# BBB-Supply.net
KiCad netlist of a schematic drawn in Altium Designer
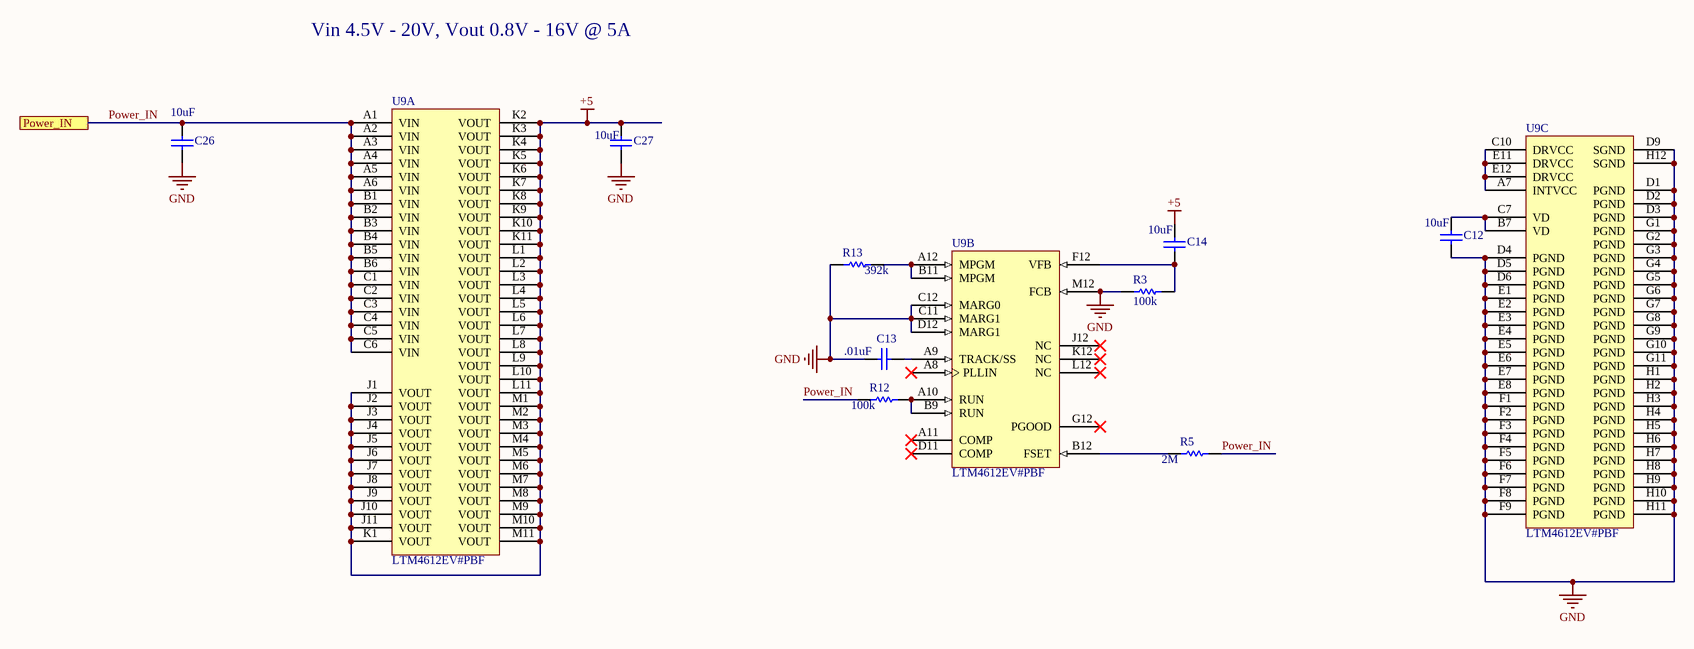
[diagram p0: BBB-Supply.SchDoc]

(export (version "E")
  (design (tool "Eeschema 10.0.6"))
  (components
    (comp (ref "C12")
      (value "10uF")
      (footprint "CAPC0805(2012)145_N")
      (description "CAP CER 10UF 25V X7R 0805")
      (fields
        (field (name "MANUFACTURER") "TDK")
        (field (name "MANUFACTURER PART NUMBER") "C2012X5R1V106K125AC")
      )
      (libsource (lib "Altium Content Vault") (part "CMP-1036-04795-1"))
    )
    (comp (ref "C13")
      (value ".01uF")
      (footprint "CAPC0805(2012)145_N")
      (fields
        (field (name "MANUFACTURER") "Yageo")
        (field (name "MANUFACTURER PART NUMBER") "AC0805KRX7R7BB103")
        (field (name "TOLERANCE") "±10%")
      )
      (libsource (lib "Altium Content Vault") (part "CMP-1036-04795-1"))
    )
    (comp (ref "C14")
      (value "10uF")
      (footprint "CAPC0805(2012)145_N")
      (description "CAP CER 10UF 25V X7R 0805")
      (fields
        (field (name "MANUFACTURER") "TDK")
        (field (name "MANUFACTURER PART NUMBER") "C2012X5R1V106K125AC")
      )
      (libsource (lib "Altium Content Vault") (part "CMP-1036-04795-1"))
    )
    (comp (ref "C26")
      (value "10uF")
      (footprint "CAPC0805(2012)145_N")
      (description "CAP CER 10UF 25V X7R 0805")
      (fields
        (field (name "MANUFACTURER") "TDK")
        (field (name "MANUFACTURER PART NUMBER") "C2012X5R1V106K125AC")
      )
      (libsource (lib "Altium Content Vault") (part "CMP-1036-04795-1"))
    )
    (comp (ref "C27")
      (value "10uF")
      (footprint "CAPC0805(2012)145_N")
      (description "CAP CER 10UF 25V X7R 0805")
      (fields
        (field (name "MANUFACTURER") "TDK")
        (field (name "MANUFACTURER PART NUMBER") "C2012X5R1V106K125AC")
      )
      (libsource (lib "Altium Content Vault") (part "CMP-1036-04795-1"))
    )
    (comp (ref "R3")
      (value "100k")
      (footprint "RESC0805(2012)_M")
      (description "RES SMD 0.8 OHM 1% 1/8W 0805")
      (libsource (lib "Altium Content Vault") (part "CMP-1013-00017-1"))
    )
    (comp (ref "R5")
      (value "2M")
      (footprint "RESC0805(2012)_M")
      (description "RES SMD 0.8 OHM 1% 1/8W 0805")
      (libsource (lib "Altium Content Vault") (part "CMP-1013-00017-1"))
    )
    (comp (ref "R12")
      (value "100k")
      (footprint "RESC0805(2012)_M")
      (description "RES SMD 0.8 OHM 1% 1/8W 0805")
      (libsource (lib "Altium Content Vault") (part "CMP-1013-00017-1"))
    )
    (comp (ref "R13")
      (value "392k")
      (footprint "RESC0805(2012)_M")
      (description "RES SMD 0.8 OHM 1% 1/8W 0805")
      (libsource (lib "Altium Content Vault") (part "CMP-1013-00017-1"))
    )
    (comp (ref "U9")
      (value "LTM4612EV#PBF")
      (footprint "LT-LGA-133-05-08-1766_V")
      (fields (field (name "MANUFACTURER") "Linear Technology"))
      (libsource (lib "Altium Content Vault") (part "LT-LTM4612-LGA-133"))
    )
  )
  (nets
    (net (code "1") (name "+5") (class "Default")
      (node (ref "C14") (pin "1") (pinfunction "1_1") (pintype "passive"))
      (node (ref "C27") (pin "1") (pinfunction "1_1") (pintype "passive"))
      (node (ref "U9") (pin "J1") (pinfunction "VOUT_J1") (pintype "power_in"))
      (node (ref "U9") (pin "J10") (pinfunction "VOUT_J10") (pintype "power_in"))
      (node (ref "U9") (pin "J11") (pinfunction "VOUT_J11") (pintype "power_in"))
      (node (ref "U9") (pin "J2") (pinfunction "VOUT_J2") (pintype "power_in"))
      (node (ref "U9") (pin "J3") (pinfunction "VOUT_J3") (pintype "power_in"))
      (node (ref "U9") (pin "J4") (pinfunction "VOUT_J4") (pintype "power_in"))
      (node (ref "U9") (pin "J5") (pinfunction "VOUT_J5") (pintype "power_in"))
      (node (ref "U9") (pin "J6") (pinfunction "VOUT_J6") (pintype "power_in"))
      (node (ref "U9") (pin "J7") (pinfunction "VOUT_J7") (pintype "power_in"))
      (node (ref "U9") (pin "J8") (pinfunction "VOUT_J8") (pintype "power_in"))
      (node (ref "U9") (pin "J9") (pinfunction "VOUT_J9") (pintype "power_in"))
      (node (ref "U9") (pin "K1") (pinfunction "VOUT_K1") (pintype "power_in"))
      (node (ref "U9") (pin "K10") (pinfunction "VOUT_K10") (pintype "power_in"))
      (node (ref "U9") (pin "K11") (pinfunction "VOUT_K11") (pintype "power_in"))
      (node (ref "U9") (pin "K2") (pinfunction "VOUT_K2") (pintype "power_in"))
      (node (ref "U9") (pin "K3") (pinfunction "VOUT_K3") (pintype "power_in"))
      (node (ref "U9") (pin "K4") (pinfunction "VOUT_K4") (pintype "power_in"))
      (node (ref "U9") (pin "K5") (pinfunction "VOUT_K5") (pintype "power_in"))
      (node (ref "U9") (pin "K6") (pinfunction "VOUT_K6") (pintype "power_in"))
      (node (ref "U9") (pin "K7") (pinfunction "VOUT_K7") (pintype "power_in"))
      (node (ref "U9") (pin "K8") (pinfunction "VOUT_K8") (pintype "power_in"))
      (node (ref "U9") (pin "K9") (pinfunction "VOUT_K9") (pintype "power_in"))
      (node (ref "U9") (pin "L1") (pinfunction "VOUT_L1") (pintype "power_in"))
      (node (ref "U9") (pin "L10") (pinfunction "VOUT_L10") (pintype "power_in"))
      (node (ref "U9") (pin "L11") (pinfunction "VOUT_L11") (pintype "power_in"))
      (node (ref "U9") (pin "L2") (pinfunction "VOUT_L2") (pintype "power_in"))
      (node (ref "U9") (pin "L3") (pinfunction "VOUT_L3") (pintype "power_in"))
      (node (ref "U9") (pin "L4") (pinfunction "VOUT_L4") (pintype "power_in"))
      (node (ref "U9") (pin "L5") (pinfunction "VOUT_L5") (pintype "power_in"))
      (node (ref "U9") (pin "L6") (pinfunction "VOUT_L6") (pintype "power_in"))
      (node (ref "U9") (pin "L7") (pinfunction "VOUT_L7") (pintype "power_in"))
      (node (ref "U9") (pin "L8") (pinfunction "VOUT_L8") (pintype "power_in"))
      (node (ref "U9") (pin "L9") (pinfunction "VOUT_L9") (pintype "power_in"))
      (node (ref "U9") (pin "M1") (pinfunction "VOUT_M1") (pintype "power_in"))
      (node (ref "U9") (pin "M10") (pinfunction "VOUT_M10") (pintype "power_in"))
      (node (ref "U9") (pin "M11") (pinfunction "VOUT_M11") (pintype "power_in"))
      (node (ref "U9") (pin "M2") (pinfunction "VOUT_M2") (pintype "power_in"))
      (node (ref "U9") (pin "M3") (pinfunction "VOUT_M3") (pintype "power_in"))
      (node (ref "U9") (pin "M4") (pinfunction "VOUT_M4") (pintype "power_in"))
      (node (ref "U9") (pin "M5") (pinfunction "VOUT_M5") (pintype "power_in"))
      (node (ref "U9") (pin "M6") (pinfunction "VOUT_M6") (pintype "power_in"))
      (node (ref "U9") (pin "M7") (pinfunction "VOUT_M7") (pintype "power_in"))
      (node (ref "U9") (pin "M8") (pinfunction "VOUT_M8") (pintype "power_in"))
      (node (ref "U9") (pin "M9") (pinfunction "VOUT_M9") (pintype "power_in"))
    )
    (net (code "2") (name "/Power_IN") (class "Default")
      (node (ref "C26") (pin "1") (pinfunction "1_1") (pintype "passive"))
      (node (ref "R12") (pin "2") (pinfunction "2_2") (pintype "passive"))
      (node (ref "R5") (pin "1") (pinfunction "1_1") (pintype "passive"))
      (node (ref "U9") (pin "A1") (pinfunction "VIN_A1") (pintype "power_in"))
      (node (ref "U9") (pin "A2") (pinfunction "VIN_A2") (pintype "power_in"))
      (node (ref "U9") (pin "A3") (pinfunction "VIN_A3") (pintype "power_in"))
      (node (ref "U9") (pin "A4") (pinfunction "VIN_A4") (pintype "power_in"))
      (node (ref "U9") (pin "A5") (pinfunction "VIN_A5") (pintype "power_in"))
      (node (ref "U9") (pin "A6") (pinfunction "VIN_A6") (pintype "power_in"))
      (node (ref "U9") (pin "B1") (pinfunction "VIN_B1") (pintype "power_in"))
      (node (ref "U9") (pin "B2") (pinfunction "VIN_B2") (pintype "power_in"))
      (node (ref "U9") (pin "B3") (pinfunction "VIN_B3") (pintype "power_in"))
      (node (ref "U9") (pin "B4") (pinfunction "VIN_B4") (pintype "power_in"))
      (node (ref "U9") (pin "B5") (pinfunction "VIN_B5") (pintype "power_in"))
      (node (ref "U9") (pin "B6") (pinfunction "VIN_B6") (pintype "power_in"))
      (node (ref "U9") (pin "C1") (pinfunction "VIN_C1") (pintype "power_in"))
      (node (ref "U9") (pin "C2") (pinfunction "VIN_C2") (pintype "power_in"))
      (node (ref "U9") (pin "C3") (pinfunction "VIN_C3") (pintype "power_in"))
      (node (ref "U9") (pin "C4") (pinfunction "VIN_C4") (pintype "power_in"))
      (node (ref "U9") (pin "C5") (pinfunction "VIN_C5") (pintype "power_in"))
      (node (ref "U9") (pin "C6") (pinfunction "VIN_C6") (pintype "power_in"))
    )
    (net (code "3") (name "GND") (class "Default")
      (node (ref "C12") (pin "2") (pinfunction "2_2") (pintype "passive"))
      (node (ref "C13") (pin "1") (pinfunction "1_1") (pintype "passive"))
      (node (ref "C26") (pin "2") (pinfunction "2_2") (pintype "passive"))
      (node (ref "C27") (pin "2") (pinfunction "2_2") (pintype "passive"))
      (node (ref "R13") (pin "2") (pinfunction "2_2") (pintype "passive"))
      (node (ref "R3") (pin "1") (pinfunction "1_1") (pintype "passive"))
      (node (ref "U9") (pin "C11") (pinfunction "MARG1_C11") (pintype "input"))
      (node (ref "U9") (pin "C12") (pinfunction "MARG0_C12") (pintype "input"))
      (node (ref "U9") (pin "D1") (pinfunction "PGND_D1") (pintype "power_in"))
      (node (ref "U9") (pin "D12") (pinfunction "MARG1_D12") (pintype "input"))
      (node (ref "U9") (pin "D2") (pinfunction "PGND_D2") (pintype "power_in"))
      (node (ref "U9") (pin "D3") (pinfunction "PGND_D3") (pintype "power_in"))
      (node (ref "U9") (pin "D4") (pinfunction "PGND_D4") (pintype "power_in"))
      (node (ref "U9") (pin "D5") (pinfunction "PGND_D5") (pintype "power_in"))
      (node (ref "U9") (pin "D6") (pinfunction "PGND_D6") (pintype "power_in"))
      (node (ref "U9") (pin "D9") (pinfunction "SGND_D9") (pintype "power_in"))
      (node (ref "U9") (pin "E1") (pinfunction "PGND_E1") (pintype "power_in"))
      (node (ref "U9") (pin "E2") (pinfunction "PGND_E2") (pintype "power_in"))
      (node (ref "U9") (pin "E3") (pinfunction "PGND_E3") (pintype "power_in"))
      (node (ref "U9") (pin "E4") (pinfunction "PGND_E4") (pintype "power_in"))
      (node (ref "U9") (pin "E5") (pinfunction "PGND_E5") (pintype "power_in"))
      (node (ref "U9") (pin "E6") (pinfunction "PGND_E6") (pintype "power_in"))
      (node (ref "U9") (pin "E7") (pinfunction "PGND_E7") (pintype "power_in"))
      (node (ref "U9") (pin "E8") (pinfunction "PGND_E8") (pintype "power_in"))
      (node (ref "U9") (pin "F1") (pinfunction "PGND_F1") (pintype "power_in"))
      (node (ref "U9") (pin "F2") (pinfunction "PGND_F2") (pintype "power_in"))
      (node (ref "U9") (pin "F3") (pinfunction "PGND_F3") (pintype "power_in"))
      (node (ref "U9") (pin "F4") (pinfunction "PGND_F4") (pintype "power_in"))
      (node (ref "U9") (pin "F5") (pinfunction "PGND_F5") (pintype "power_in"))
      (node (ref "U9") (pin "F6") (pinfunction "PGND_F6") (pintype "power_in"))
      (node (ref "U9") (pin "F7") (pinfunction "PGND_F7") (pintype "power_in"))
      (node (ref "U9") (pin "F8") (pinfunction "PGND_F8") (pintype "power_in"))
      (node (ref "U9") (pin "F9") (pinfunction "PGND_F9") (pintype "power_in"))
      (node (ref "U9") (pin "G1") (pinfunction "PGND_G1") (pintype "power_in"))
      (node (ref "U9") (pin "G10") (pinfunction "PGND_G10") (pintype "power_in"))
      (node (ref "U9") (pin "G11") (pinfunction "PGND_G11") (pintype "power_in"))
      (node (ref "U9") (pin "G2") (pinfunction "PGND_G2") (pintype "power_in"))
      (node (ref "U9") (pin "G3") (pinfunction "PGND_G3") (pintype "power_in"))
      (node (ref "U9") (pin "G4") (pinfunction "PGND_G4") (pintype "power_in"))
      (node (ref "U9") (pin "G5") (pinfunction "PGND_G5") (pintype "power_in"))
      (node (ref "U9") (pin "G6") (pinfunction "PGND_G6") (pintype "power_in"))
      (node (ref "U9") (pin "G7") (pinfunction "PGND_G7") (pintype "power_in"))
      (node (ref "U9") (pin "G8") (pinfunction "PGND_G8") (pintype "power_in"))
      (node (ref "U9") (pin "G9") (pinfunction "PGND_G9") (pintype "power_in"))
      (node (ref "U9") (pin "H1") (pinfunction "PGND_H1") (pintype "power_in"))
      (node (ref "U9") (pin "H10") (pinfunction "PGND_H10") (pintype "power_in"))
      (node (ref "U9") (pin "H11") (pinfunction "PGND_H11") (pintype "power_in"))
      (node (ref "U9") (pin "H12") (pinfunction "SGND_H12") (pintype "power_in"))
      (node (ref "U9") (pin "H2") (pinfunction "PGND_H2") (pintype "power_in"))
      (node (ref "U9") (pin "H3") (pinfunction "PGND_H3") (pintype "power_in"))
      (node (ref "U9") (pin "H4") (pinfunction "PGND_H4") (pintype "power_in"))
      (node (ref "U9") (pin "H5") (pinfunction "PGND_H5") (pintype "power_in"))
      (node (ref "U9") (pin "H6") (pinfunction "PGND_H6") (pintype "power_in"))
      (node (ref "U9") (pin "H7") (pinfunction "PGND_H7") (pintype "power_in"))
      (node (ref "U9") (pin "H8") (pinfunction "PGND_H8") (pintype "power_in"))
      (node (ref "U9") (pin "H9") (pinfunction "PGND_H9") (pintype "power_in"))
      (node (ref "U9") (pin "M12") (pinfunction "FCB_M12") (pintype "input"))
    )
    (net (code "4") (name "Net-(C12-Pad1)") (class "Default")
      (node (ref "C12") (pin "1") (pinfunction "1_1") (pintype "passive"))
      (node (ref "U9") (pin "B7") (pinfunction "VD_B7") (pintype "power_in"))
      (node (ref "U9") (pin "C7") (pinfunction "VD_C7") (pintype "power_in"))
    )
    (net (code "5") (name "Net-(R12-Pad1)") (class "Default")
      (node (ref "R12") (pin "1") (pinfunction "1_1") (pintype "passive"))
      (node (ref "U9") (pin "A10") (pinfunction "RUN_A10") (pintype "input"))
      (node (ref "U9") (pin "B9") (pinfunction "RUN_B9") (pintype "input"))
    )
    (net (code "6") (name "Net-(R13-Pad1)") (class "Default")
      (node (ref "R13") (pin "1") (pinfunction "1_1") (pintype "passive"))
      (node (ref "U9") (pin "A12") (pinfunction "MPGM_A12") (pintype "input"))
      (node (ref "U9") (pin "B11") (pinfunction "MPGM_B11") (pintype "input"))
    )
    (net (code "7") (name "Net-(U9B-FSET)") (class "Default")
      (node (ref "R5") (pin "2") (pinfunction "2_2") (pintype "passive"))
      (node (ref "U9") (pin "B12") (pinfunction "FSET_B12") (pintype "input"))
    )
    (net (code "8") (name "Net-(U9B-TRACK{slash}SS)") (class "Default")
      (node (ref "C13") (pin "2") (pinfunction "2_2") (pintype "passive"))
      (node (ref "U9") (pin "A9") (pinfunction "TRACK/SS_A9") (pintype "input"))
    )
    (net (code "9") (name "Net-(U9B-VFB)") (class "Default")
      (node (ref "C14") (pin "2") (pinfunction "2_2") (pintype "passive"))
      (node (ref "R3") (pin "2") (pinfunction "2_2") (pintype "passive"))
      (node (ref "U9") (pin "F12") (pinfunction "VFB_F12") (pintype "input"))
    )
    (net (code "10") (name "Net-(U9C-INTVCC)") (class "Default")
      (node (ref "U9") (pin "A7") (pinfunction "INTVCC_A7") (pintype "power_in"))
      (node (ref "U9") (pin "C10") (pinfunction "DRVCC_C10") (pintype "power_in"))
      (node (ref "U9") (pin "E11") (pinfunction "DRVCC_E11") (pintype "power_in"))
      (node (ref "U9") (pin "E12") (pinfunction "DRVCC_E12") (pintype "power_in"))
    )
    (net (code "11") (name "unconnected-(U9B-COMP-PadA11)") (class "Default")
      (node (ref "U9") (pin "A11") (pinfunction "COMP_A11") (pintype "passive+no_connect"))
    )
    (net (code "12") (name "unconnected-(U9B-COMP-PadD11)") (class "Default")
      (node (ref "U9") (pin "D11") (pinfunction "COMP_D11") (pintype "passive+no_connect"))
    )
    (net (code "13") (name "unconnected-(U9B-NC-PadJ12)") (class "Default")
      (node (ref "U9") (pin "J12") (pinfunction "NC_J12") (pintype "passive+no_connect"))
    )
    (net (code "14") (name "unconnected-(U9B-NC-PadK12)") (class "Default")
      (node (ref "U9") (pin "K12") (pinfunction "NC_K12") (pintype "passive+no_connect"))
    )
    (net (code "15") (name "unconnected-(U9B-NC-PadL12)") (class "Default")
      (node (ref "U9") (pin "L12") (pinfunction "NC_L12") (pintype "passive+no_connect"))
    )
    (net (code "16") (name "unconnected-(U9B-PGOOD-PadG12)") (class "Default")
      (node (ref "U9") (pin "G12") (pinfunction "PGOOD_G12") (pintype "open_collector+no_connect"))
    )
    (net (code "17") (name "unconnected-(U9B-PLLIN-PadA8)") (class "Default")
      (node (ref "U9") (pin "A8") (pinfunction "PLLIN_A8") (pintype "input+no_connect"))
    )
  )
)
